# Top.net
KiCad netlist of a schematic drawn in Altium Designer
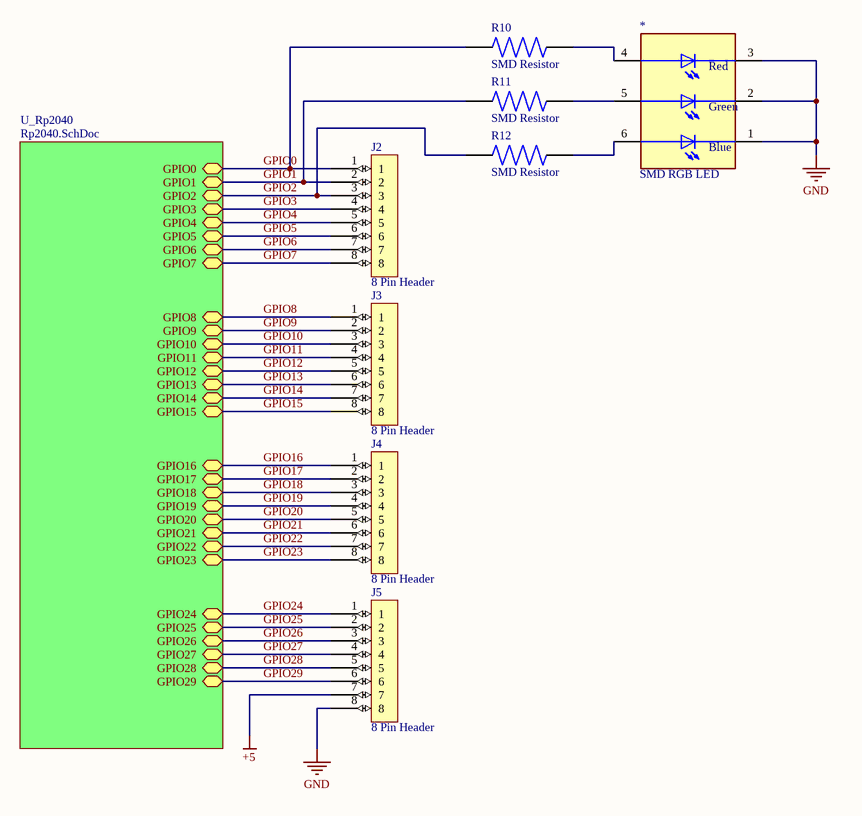
[diagram p0: Top.SchDoc]

(export (version "E")
  (design (tool "Eeschema 10.0.6"))
  (components
    (comp (ref "*")
      (value "SMD RGB LED")
      (footprint "SMD RGB LED-Footprint-1")
      (libsource (lib "Tobias") (part "SMD RGB LED-Symbol-1"))
    )
    (comp (ref "J2")
      (value "8 Pin Header")
      (footprint "8 Pin Header-Footprint-1")
      (description "8 Pin Breakout Header")
      (libsource (lib "Tobias") (part "8 Pin Header-Symbol-1"))
    )
    (comp (ref "J3")
      (value "8 Pin Header")
      (footprint "8 Pin Header-Footprint-1")
      (description "8 Pin Breakout Header")
      (libsource (lib "Tobias") (part "8 Pin Header-Symbol-1"))
    )
    (comp (ref "J4")
      (value "8 Pin Header")
      (footprint "8 Pin Header-Footprint-1")
      (description "8 Pin Breakout Header")
      (libsource (lib "Tobias") (part "8 Pin Header-Symbol-1"))
    )
    (comp (ref "J5")
      (value "8 Pin Header")
      (footprint "8 Pin Header-Footprint-1")
      (description "8 Pin Breakout Header")
      (libsource (lib "Tobias") (part "8 Pin Header-Symbol-1"))
    )
    (comp (ref "R10")
      (value "SMD Resistor")
      (footprint "SMD Resistor-Footprint-1")
      (description "Generic SMD Resistor")
      (libsource (lib "Tobias") (part "SMD Resistor-Symbol-1"))
    )
    (comp (ref "R11")
      (value "SMD Resistor")
      (footprint "SMD Resistor-Footprint-1")
      (description "Generic SMD Resistor")
      (libsource (lib "Tobias") (part "SMD Resistor-Symbol-1"))
    )
    (comp (ref "R12")
      (value "SMD Resistor")
      (footprint "SMD Resistor-Footprint-1")
      (description "Generic SMD Resistor")
      (libsource (lib "Tobias") (part "SMD Resistor-Symbol-1"))
    )
  )
  (nets
    (net (code "1") (name "+5") (class "Default")
      (node (ref "J5") (pin "7") (pinfunction "7_7") (pintype "bidirectional"))
    )
    (net (code "2") (name "/GPIO0") (class "Default")
      (node (ref "J2") (pin "1") (pinfunction "1_1") (pintype "bidirectional"))
      (node (ref "R10") (pin "1") (pinfunction "1_1") (pintype "passive"))
    )
    (net (code "3") (name "/GPIO1") (class "Default")
      (node (ref "J2") (pin "2") (pinfunction "2_2") (pintype "bidirectional"))
      (node (ref "R11") (pin "1") (pinfunction "1_1") (pintype "passive"))
    )
    (net (code "4") (name "/GPIO2") (class "Default")
      (node (ref "J2") (pin "3") (pinfunction "3_3") (pintype "bidirectional"))
      (node (ref "R12") (pin "1") (pinfunction "1_1") (pintype "passive"))
    )
    (net (code "5") (name "/GPIO3") (class "Default")
      (node (ref "J2") (pin "4") (pinfunction "4_4") (pintype "bidirectional"))
    )
    (net (code "6") (name "/GPIO4") (class "Default")
      (node (ref "J2") (pin "5") (pinfunction "5_5") (pintype "bidirectional"))
    )
    (net (code "7") (name "/GPIO5") (class "Default")
      (node (ref "J2") (pin "6") (pinfunction "6_6") (pintype "bidirectional"))
    )
    (net (code "8") (name "/GPIO6") (class "Default")
      (node (ref "J2") (pin "7") (pinfunction "7_7") (pintype "bidirectional"))
    )
    (net (code "9") (name "/GPIO7") (class "Default")
      (node (ref "J2") (pin "8") (pinfunction "8_8") (pintype "bidirectional"))
    )
    (net (code "10") (name "/GPIO8") (class "Default")
      (node (ref "J3") (pin "1") (pinfunction "1_1") (pintype "bidirectional"))
    )
    (net (code "11") (name "/GPIO9") (class "Default")
      (node (ref "J3") (pin "2") (pinfunction "2_2") (pintype "bidirectional"))
    )
    (net (code "12") (name "/GPIO10") (class "Default")
      (node (ref "J3") (pin "3") (pinfunction "3_3") (pintype "bidirectional"))
    )
    (net (code "13") (name "/GPIO11") (class "Default")
      (node (ref "J3") (pin "4") (pinfunction "4_4") (pintype "bidirectional"))
    )
    (net (code "14") (name "/GPIO12") (class "Default")
      (node (ref "J3") (pin "5") (pinfunction "5_5") (pintype "bidirectional"))
    )
    (net (code "15") (name "/GPIO13") (class "Default")
      (node (ref "J3") (pin "6") (pinfunction "6_6") (pintype "bidirectional"))
    )
    (net (code "16") (name "/GPIO14") (class "Default")
      (node (ref "J3") (pin "7") (pinfunction "7_7") (pintype "bidirectional"))
    )
    (net (code "17") (name "/GPIO15") (class "Default")
      (node (ref "J3") (pin "8") (pinfunction "8_8") (pintype "bidirectional"))
    )
    (net (code "18") (name "/GPIO16") (class "Default")
      (node (ref "J4") (pin "1") (pinfunction "1_1") (pintype "bidirectional"))
    )
    (net (code "19") (name "/GPIO17") (class "Default")
      (node (ref "J4") (pin "2") (pinfunction "2_2") (pintype "bidirectional"))
    )
    (net (code "20") (name "/GPIO18") (class "Default")
      (node (ref "J4") (pin "3") (pinfunction "3_3") (pintype "bidirectional"))
    )
    (net (code "21") (name "/GPIO19") (class "Default")
      (node (ref "J4") (pin "4") (pinfunction "4_4") (pintype "bidirectional"))
    )
    (net (code "22") (name "/GPIO20") (class "Default")
      (node (ref "J4") (pin "5") (pinfunction "5_5") (pintype "bidirectional"))
    )
    (net (code "23") (name "/GPIO21") (class "Default")
      (node (ref "J4") (pin "6") (pinfunction "6_6") (pintype "bidirectional"))
    )
    (net (code "24") (name "/GPIO22") (class "Default")
      (node (ref "J4") (pin "7") (pinfunction "7_7") (pintype "bidirectional"))
    )
    (net (code "25") (name "/GPIO23") (class "Default")
      (node (ref "J4") (pin "8") (pinfunction "8_8") (pintype "bidirectional"))
    )
    (net (code "26") (name "/GPIO24") (class "Default")
      (node (ref "J5") (pin "1") (pinfunction "1_1") (pintype "bidirectional"))
    )
    (net (code "27") (name "/GPIO25") (class "Default")
      (node (ref "J5") (pin "2") (pinfunction "2_2") (pintype "bidirectional"))
    )
    (net (code "28") (name "/GPIO26") (class "Default")
      (node (ref "J5") (pin "3") (pinfunction "3_3") (pintype "bidirectional"))
    )
    (net (code "29") (name "/GPIO27") (class "Default")
      (node (ref "J5") (pin "4") (pinfunction "4_4") (pintype "bidirectional"))
    )
    (net (code "30") (name "/GPIO28") (class "Default")
      (node (ref "J5") (pin "5") (pinfunction "5_5") (pintype "bidirectional"))
    )
    (net (code "31") (name "/GPIO29") (class "Default")
      (node (ref "J5") (pin "6") (pinfunction "6_6") (pintype "bidirectional"))
    )
    (net (code "32") (name "GND") (class "Default")
      (node (ref "*") (pin "1") (pinfunction "1_1") (pintype "passive"))
      (node (ref "*") (pin "2") (pinfunction "2_2") (pintype "passive"))
      (node (ref "*") (pin "3") (pinfunction "3_3") (pintype "passive"))
      (node (ref "J5") (pin "8") (pinfunction "8_8") (pintype "bidirectional"))
    )
    (net (code "33") (name "Net-(*-Pad4)") (class "Default")
      (node (ref "*") (pin "4") (pinfunction "4_4") (pintype "passive"))
      (node (ref "R10") (pin "2") (pinfunction "2_2") (pintype "passive"))
    )
    (net (code "34") (name "Net-(*-Pad5)") (class "Default")
      (node (ref "*") (pin "5") (pinfunction "5_5") (pintype "passive"))
      (node (ref "R11") (pin "2") (pinfunction "2_2") (pintype "passive"))
    )
    (net (code "35") (name "Net-(*-Pad6)") (class "Default")
      (node (ref "*") (pin "6") (pinfunction "6_6") (pintype "passive"))
      (node (ref "R12") (pin "2") (pinfunction "2_2") (pintype "passive"))
    )
  )
)
